# TPS922051.net
KiCad netlist of a schematic drawn in Altium Designer
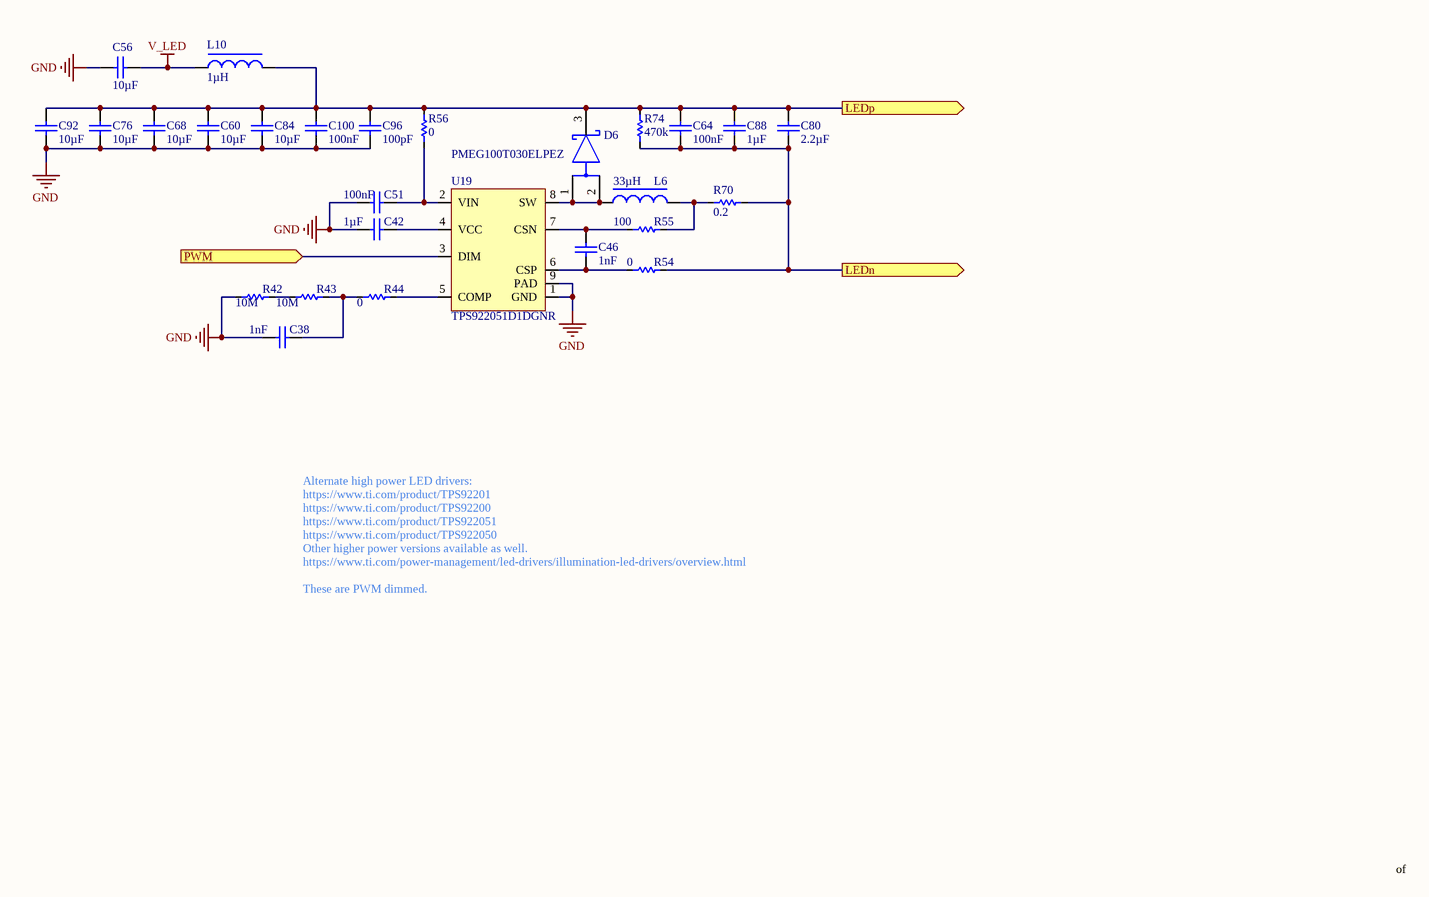
[diagram p0: TPS922051.SchDoc]

(export (version "E")
  (design (tool "Eeschema 10.0.6"))
  (components
    (comp (ref "C38")
      (value "1nF")
      (footprint "CAPC1608X10N_0603_MED")
      (fields (field (name "TOLERANCE") "10%") (field (name "Comment") "C0603C102K5RACTU"))
      (libsource (lib "Equus Computer Systems") (part "CAP-NP-2"))
    )
    (comp (ref "C42")
      (value "1µF")
      (footprint "CAPC1608X10N_0603_MED")
      (fields (field (name "TOLERANCE") "10%") (field (name "Comment") "C1608X7R1C105K080AC"))
      (libsource (lib "Equus Computer Systems") (part "CAP-NP-2"))
    )
    (comp (ref "C46")
      (value "1nF")
      (footprint "CAPC1608X10N_0603_MED")
      (fields (field (name "TOLERANCE") "10%") (field (name "Comment") "C0603C102K5RACTU"))
      (libsource (lib "Equus Computer Systems") (part "CAP-NP-2"))
    )
    (comp (ref "C51")
      (value "100nF")
      (footprint "CAPC1608X10N_0603_MED")
      (fields (field (name "Comment") "CC0603KRX7R0BB104"))
      (libsource (lib "Equus Computer Systems") (part "CAP-NP-2"))
    )
    (comp (ref "C56")
      (value "10µF")
      (footprint "CAPC2012X14N_0805_MED")
      (description "Ceramic Capacitor, Multilayer, Ceramic, 10uF, 50V, 10%, X6S, 0805")
      (fields (field (name "TOLERANCE") "10%") (field (name "Comment") "GRM21BR61H106KE43L"))
      (libsource (lib "Equus Computer Systems") (part "CAP-NP-2"))
    )
    (comp (ref "C60")
      (value "10µF")
      (footprint "CAPC2012X14N_0805_MED")
      (description "Ceramic Capacitor, Multilayer, Ceramic, 10uF, 50V, 10%, X6S, 0805")
      (fields (field (name "TOLERANCE") "10%") (field (name "Comment") "GRM21BR61H106KE43L"))
      (libsource (lib "Equus Computer Systems") (part "CAP-NP-2"))
    )
    (comp (ref "C64")
      (value "100nF")
      (footprint "CAPC1608X10N_0603_MED")
      (fields (field (name "Comment") "CC0603KRX7R0BB104"))
      (libsource (lib "Equus Computer Systems") (part "CAP-NP-2"))
    )
    (comp (ref "C68")
      (value "10µF")
      (footprint "CAPC2012X14N_0805_MED")
      (description "Ceramic Capacitor, Multilayer, Ceramic, 10uF, 50V, 10%, X6S, 0805")
      (fields (field (name "TOLERANCE") "10%") (field (name "Comment") "GRM21BR61H106KE43L"))
      (libsource (lib "Equus Computer Systems") (part "CAP-NP-2"))
    )
    (comp (ref "C76")
      (value "10µF")
      (footprint "CAPC2012X14N_0805_MED")
      (description "Ceramic Capacitor, Multilayer, Ceramic, 10uF, 50V, 10%, X6S, 0805")
      (fields (field (name "TOLERANCE") "10%") (field (name "Comment") "GRM21BR61H106KE43L"))
      (libsource (lib "Equus Computer Systems") (part "CAP-NP-2"))
    )
    (comp (ref "C80")
      (value "2.2µF")
      (footprint "CAPC2012X14N_0805_MED")
      (description "Ceramic Capacitor, Multilayer, Ceramic, 2.2uF, 50V, 10%, X6S, 0805")
      (fields (field (name "TOLERANCE") "10%") (field (name "Comment") "CGA4J3X7R1H225K125AE"))
      (libsource (lib "Equus Computer Systems") (part "CAP-NP-2"))
    )
    (comp (ref "C84")
      (value "10µF")
      (footprint "CAPC2012X14N_0805_MED")
      (description "Ceramic Capacitor, Multilayer, Ceramic, 10uF, 50V, 10%, X6S, 0805")
      (fields (field (name "TOLERANCE") "10%") (field (name "Comment") "GRM21BR61H106KE43L"))
      (libsource (lib "Equus Computer Systems") (part "CAP-NP-2"))
    )
    (comp (ref "C88")
      (value "1µF")
      (footprint "CAPC2012X14N_0805_MED")
      (description "Ceramic Capacitor, Multilayer, Ceramic, 1uF, 50V, 10%, XRS, 0805")
      (fields (field (name "TOLERANCE") "10%") (field (name "Comment") "CL21B105KBFNNNE"))
      (libsource (lib "Equus Computer Systems") (part "CAP-NP-2"))
    )
    (comp (ref "C92")
      (value "10µF")
      (footprint "CAPC2012X14N_0805_MED")
      (description "Ceramic Capacitor, Multilayer, Ceramic, 10uF, 50V, 10%, X6S, 0805")
      (fields (field (name "TOLERANCE") "10%") (field (name "Comment") "GRM21BR61H106KE43L"))
      (libsource (lib "Equus Computer Systems") (part "CAP-NP-2"))
    )
    (comp (ref "C96")
      (value "100pF")
      (footprint "CAPC1608X10N_0603_MED")
      (description "Ceramic Capacitor, Multilayer, Ceramic, 50V, 5% Tol X7R, 100pF, Surface Mount, 0603")
      (fields (field (name "TOLERANCE") "5%") (field (name "Comment") "GCM1885C1H101JA16D"))
      (libsource (lib "Equus Computer Systems") (part "CAP-NP-2"))
    )
    (comp (ref "C100")
      (value "100nF")
      (footprint "CAPC1608X10N_0603_MED")
      (fields (field (name "Comment") "CC0603KRX7R0BB104"))
      (libsource (lib "Equus Computer Systems") (part "CAP-NP-2"))
    )
    (comp (ref "D6")
      (value "PMEG100T030ELPEZ")
      (footprint "FP-SOT1289B-MFG")
      (description "Schottky Rectifier, Single, 100V, 3A Rohs Compliant: Yes")
      (libsource (lib "Equus Computer Systems") (part "6b4b5b2f550b82c6b4a28adc8367884"))
    )
    (comp (ref "L6")
      (value "33µH")
      (footprint "SPM6545VT-330M-D-Footprint-1")
      (description "General Purpose Inductor, 33uH, 20%, 1 Element, Metal Composite-Core, SMD, 2826")
      (fields (field (name "TOLERANCE") "20%") (field (name "Comment") "SPM6545VT-330M-D"))
      (libsource (lib "Equus Computer Systems") (part "IND-CORE-2"))
    )
    (comp (ref "L10")
      (value "1µH")
      (footprint "WE-MAPI_3020")
      (description "Inductors, Fixed, WE-MAPI SMD 3020 1.0uH 4.0A 32mOhm")
      (fields (field (name "TOLERANCE") "20%") (field (name "Comment") "74438336010"))
      (libsource (lib "Equus Computer Systems") (part "IND-CORE-2"))
    )
    (comp (ref "R42")
      (value "10M")
      (footprint "RESC1608X06N_0603_MED")
      (fields
        (field (name "POWER") "100mW")
        (field (name "TOLERANCE") "5%")
        (field (name "Comment") "RC0603JR-0710ML")
      )
      (libsource (lib "Equus Computer Systems") (part "RES-2"))
    )
    (comp (ref "R43")
      (value "10M")
      (footprint "RESC1608X06N_0603_MED")
      (fields
        (field (name "POWER") "100mW")
        (field (name "TOLERANCE") "5%")
        (field (name "Comment") "RC0603JR-0710ML")
      )
      (libsource (lib "Equus Computer Systems") (part "RES-2"))
    )
    (comp (ref "R44")
      (value "0")
      (footprint "RESC1608X06N_0603_MED")
      (description "RC Series 0603 0.1 W 0 Ohm Jumper Surface Mount Thick Film Chip Resistor")
      (fields (field (name "POWER") "100mW") (field (name "TOLERANCE") "1%"))
      (libsource (lib "Equus Computer Systems") (part "RES-2"))
    )
    (comp (ref "R54")
      (value "0")
      (footprint "RESC1608X06N_0603_MED")
      (description "RC Series 0603 0.1 W 0 Ohm Jumper Surface Mount Thick Film Chip Resistor")
      (fields (field (name "POWER") "100mW") (field (name "TOLERANCE") "1%"))
      (libsource (lib "Equus Computer Systems") (part "RES-2"))
    )
    (comp (ref "R55")
      (value "100")
      (footprint "RESC1608X06N_0603_MED")
      (fields
        (field (name "TOLERANCE") "1%")
        (field (name "POWER") "100mW")
        (field (name "Comment") "RC0603FR-07100RL")
      )
      (libsource (lib "Equus Computer Systems") (part "RES-2"))
    )
    (comp (ref "R56")
      (value "0")
      (footprint "RESC1608X06N_0603_MED")
      (description "RC Series 0603 0.1 W 0 Ohm Jumper Surface Mount Thick Film Chip Resistor")
      (fields (field (name "POWER") "100mW") (field (name "TOLERANCE") "1%"))
      (libsource (lib "Equus Computer Systems") (part "RES-2"))
    )
    (comp (ref "R70")
      (value "0.2")
      (footprint "RESC640320X70_CRG2512_MFG")
      (description "Res Metal Strip 2512 0.2 Ohm 1% 1W ±50ppm/°C Sulfur Resistant Pad SMD T/R Automotive AEC-Q200")
      (fields (field (name "TOLERANCE") "1%") (field (name "Comment") "CRG2512-FZ-R200E-1"))
      (libsource (lib "Equus Computer Systems") (part "RES-2"))
    )
    (comp (ref "R74")
      (value "470k")
      (footprint "RESC1608X06N_0603_MED")
      (fields
        (field (name "TOLERANCE") "1%")
        (field (name "POWER") "100mW")
        (field (name "Comment") "RC0603FR-13470KL")
      )
      (libsource (lib "Equus Computer Systems") (part "RES-2"))
    )
    (comp (ref "U19")
      (value "TPS922051D1DGNR")
      (footprint "TPS92205x_TSOP65P490X110_HS-9N")
      (description "65V, 2A buck LED driver with analog or PWM dimming options 8-HVSSOP -40 to 85")
      (libsource (lib "Equus Computer Systems") (part "TPS922051D1DGNR-Symbol-1"))
    )
  )
  (nets
    (net (code "1") (name "/LEDn") (class "Default")
      (node (ref "C64") (pin "1") (pinfunction "1_1") (pintype "passive"))
      (node (ref "C80") (pin "1") (pinfunction "1_1") (pintype "passive"))
      (node (ref "C88") (pin "1") (pinfunction "1_1") (pintype "passive"))
      (node (ref "R54") (pin "2") (pinfunction "2_2") (pintype "passive"))
      (node (ref "R70") (pin "2") (pinfunction "2_2") (pintype "passive"))
      (node (ref "R74") (pin "1") (pinfunction "1_1") (pintype "passive"))
    )
    (net (code "2") (name "/LEDp") (class "Default")
      (node (ref "C100") (pin "2") (pinfunction "2_2") (pintype "passive"))
      (node (ref "C60") (pin "2") (pinfunction "2_2") (pintype "passive"))
      (node (ref "C64") (pin "2") (pinfunction "2_2") (pintype "passive"))
      (node (ref "C68") (pin "2") (pinfunction "2_2") (pintype "passive"))
      (node (ref "C76") (pin "2") (pinfunction "2_2") (pintype "passive"))
      (node (ref "C80") (pin "2") (pinfunction "2_2") (pintype "passive"))
      (node (ref "C84") (pin "2") (pinfunction "2_2") (pintype "passive"))
      (node (ref "C88") (pin "2") (pinfunction "2_2") (pintype "passive"))
      (node (ref "C92") (pin "2") (pinfunction "2_2") (pintype "passive"))
      (node (ref "C96") (pin "2") (pinfunction "2_2") (pintype "passive"))
      (node (ref "D6") (pin "3") (pinfunction "K_3") (pintype "passive"))
      (node (ref "L10") (pin "2") (pinfunction "2_2") (pintype "passive"))
      (node (ref "R56") (pin "2") (pinfunction "2_2") (pintype "passive"))
      (node (ref "R74") (pin "2") (pinfunction "2_2") (pintype "passive"))
    )
    (net (code "3") (name "/PWM") (class "Default")
      (node (ref "U19") (pin "3") (pinfunction "DIM_3") (pintype "passive"))
    )
    (net (code "4") (name "GND") (class "Default")
      (node (ref "C100") (pin "1") (pinfunction "1_1") (pintype "passive"))
      (node (ref "C38") (pin "1") (pinfunction "1_1") (pintype "passive"))
      (node (ref "C42") (pin "1") (pinfunction "1_1") (pintype "passive"))
      (node (ref "C51") (pin "1") (pinfunction "1_1") (pintype "passive"))
      (node (ref "C56") (pin "1") (pinfunction "1_1") (pintype "passive"))
      (node (ref "C60") (pin "1") (pinfunction "1_1") (pintype "passive"))
      (node (ref "C68") (pin "1") (pinfunction "1_1") (pintype "passive"))
      (node (ref "C76") (pin "1") (pinfunction "1_1") (pintype "passive"))
      (node (ref "C84") (pin "1") (pinfunction "1_1") (pintype "passive"))
      (node (ref "C92") (pin "1") (pinfunction "1_1") (pintype "passive"))
      (node (ref "C96") (pin "1") (pinfunction "1_1") (pintype "passive"))
      (node (ref "R42") (pin "1") (pinfunction "1_1") (pintype "passive"))
      (node (ref "U19") (pin "1") (pinfunction "GND_1") (pintype "passive"))
      (node (ref "U19") (pin "9") (pinfunction "PAD_9") (pintype "passive"))
    )
    (net (code "5") (name "Net-(C38-Pad2)") (class "Default")
      (node (ref "C38") (pin "2") (pinfunction "2_2") (pintype "passive"))
      (node (ref "R43") (pin "1") (pinfunction "1_1") (pintype "passive"))
      (node (ref "R44") (pin "2") (pinfunction "2_2") (pintype "passive"))
    )
    (net (code "6") (name "Net-(L6-Pad2)") (class "Default")
      (node (ref "L6") (pin "2") (pinfunction "2_2") (pintype "passive"))
      (node (ref "R55") (pin "2") (pinfunction "2_2") (pintype "passive"))
      (node (ref "R70") (pin "1") (pinfunction "1_1") (pintype "passive"))
    )
    (net (code "7") (name "Net-(R42-Pad2)") (class "Default")
      (node (ref "R42") (pin "2") (pinfunction "2_2") (pintype "passive"))
      (node (ref "R43") (pin "2") (pinfunction "2_2") (pintype "passive"))
    )
    (net (code "8") (name "Net-(U19-COMP)") (class "Default")
      (node (ref "R44") (pin "1") (pinfunction "1_1") (pintype "passive"))
      (node (ref "U19") (pin "5") (pinfunction "COMP_5") (pintype "passive"))
    )
    (net (code "9") (name "Net-(U19-CSN)") (class "Default")
      (node (ref "C46") (pin "2") (pinfunction "2_2") (pintype "passive"))
      (node (ref "R55") (pin "1") (pinfunction "1_1") (pintype "passive"))
      (node (ref "U19") (pin "7") (pinfunction "CSN_7") (pintype "passive"))
    )
    (net (code "10") (name "Net-(U19-CSP)") (class "Default")
      (node (ref "C46") (pin "1") (pinfunction "1_1") (pintype "passive"))
      (node (ref "R54") (pin "1") (pinfunction "1_1") (pintype "passive"))
      (node (ref "U19") (pin "6") (pinfunction "CSP_6") (pintype "passive"))
    )
    (net (code "11") (name "Net-(U19-SW)") (class "Default")
      (node (ref "D6") (pin "1") (pinfunction "A_1") (pintype "passive"))
      (node (ref "D6") (pin "2") (pinfunction "A_2") (pintype "passive"))
      (node (ref "L6") (pin "1") (pinfunction "1_1") (pintype "passive"))
      (node (ref "U19") (pin "8") (pinfunction "SW_8") (pintype "passive"))
    )
    (net (code "12") (name "Net-(U19-VCC)") (class "Default")
      (node (ref "C42") (pin "2") (pinfunction "2_2") (pintype "passive"))
      (node (ref "U19") (pin "4") (pinfunction "VCC_4") (pintype "passive"))
    )
    (net (code "13") (name "Net-(U19-VIN)") (class "Default")
      (node (ref "C51") (pin "2") (pinfunction "2_2") (pintype "passive"))
      (node (ref "R56") (pin "1") (pinfunction "1_1") (pintype "passive"))
      (node (ref "U19") (pin "2") (pinfunction "VIN_2") (pintype "passive"))
    )
    (net (code "14") (name "V_LED") (class "Default")
      (node (ref "C56") (pin "2") (pinfunction "2_2") (pintype "passive"))
      (node (ref "L10") (pin "1") (pinfunction "1_1") (pintype "passive"))
    )
  )
)
